# UCirKitUserStudy5.net
KiCad netlist of a schematic drawn in EAGLE
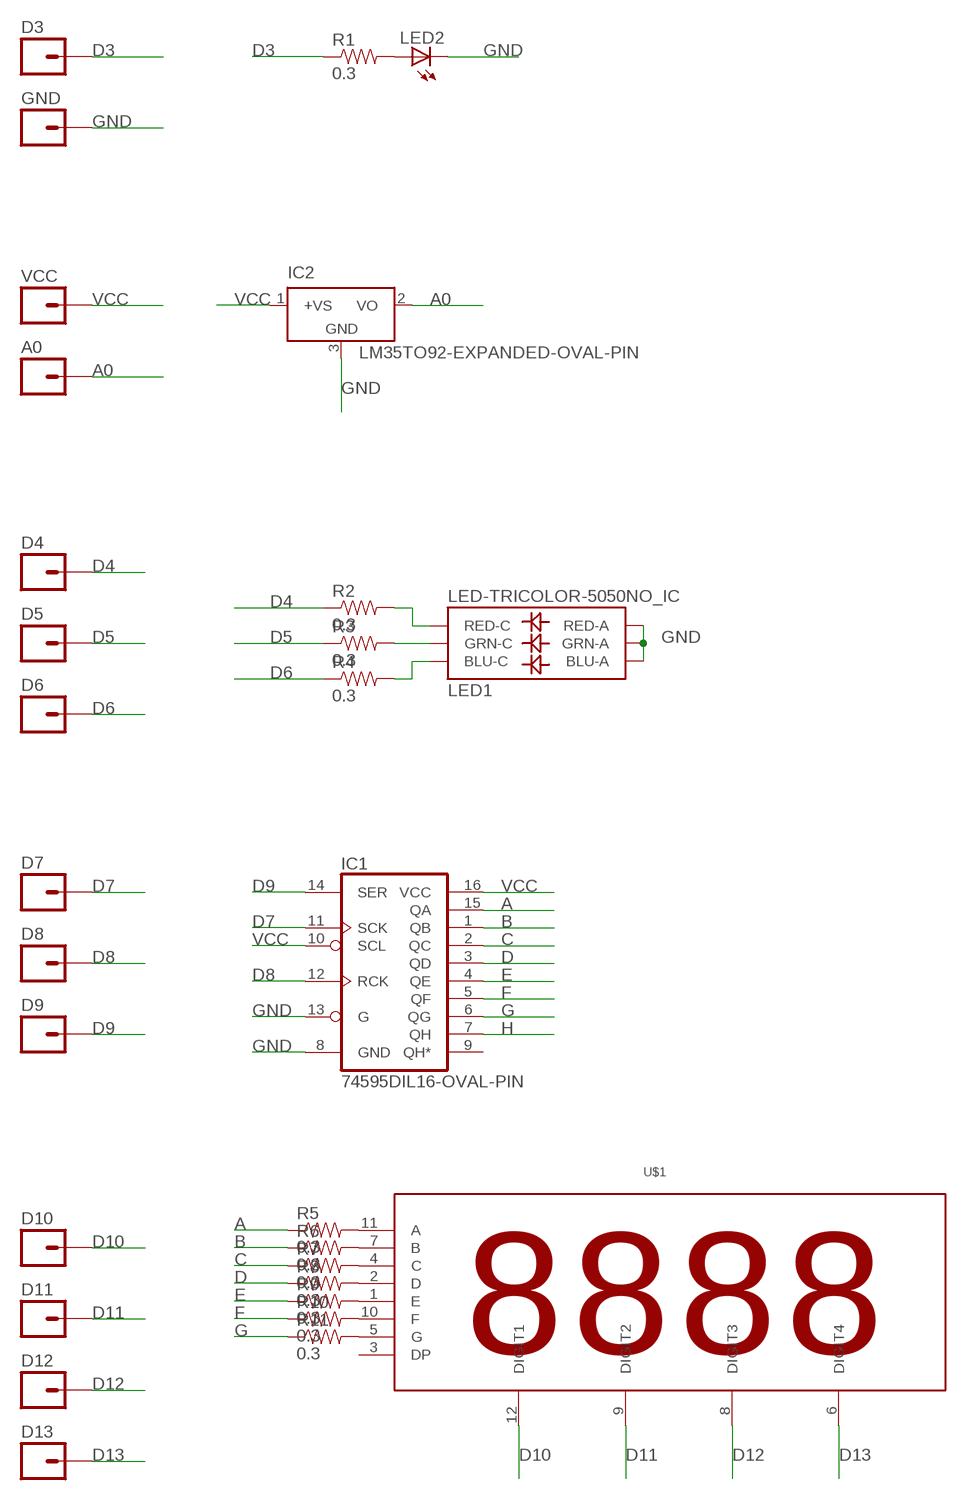
[diagram p0: schematic, sheet 1]

(export (version "E")
  (design (tool "Eeschema 10.0.6"))
  (components
    (comp (ref "A0")
      (value "M01OVAL_PIN")
      (footprint "eagle-import:1X01_OVAL_PIN")
      (libsource (lib "eagle-import") (part "M01OVAL_PIN"))
    )
    (comp (ref "D3")
      (value "M01OVAL_PIN")
      (footprint "eagle-import:1X01_OVAL_PIN")
      (libsource (lib "eagle-import") (part "M01OVAL_PIN"))
    )
    (comp (ref "D4")
      (value "M01OVAL_PIN")
      (footprint "eagle-import:1X01_OVAL_PIN")
      (libsource (lib "eagle-import") (part "M01OVAL_PIN"))
    )
    (comp (ref "D5")
      (value "M01OVAL_PIN")
      (footprint "eagle-import:1X01_OVAL_PIN")
      (libsource (lib "eagle-import") (part "M01OVAL_PIN"))
    )
    (comp (ref "D6")
      (value "M01OVAL_PIN")
      (footprint "eagle-import:1X01_OVAL_PIN")
      (libsource (lib "eagle-import") (part "M01OVAL_PIN"))
    )
    (comp (ref "D7")
      (value "M01OVAL_PIN")
      (footprint "eagle-import:1X01_OVAL_PIN")
      (libsource (lib "eagle-import") (part "M01OVAL_PIN"))
    )
    (comp (ref "D8")
      (value "M01OVAL_PIN")
      (footprint "eagle-import:1X01_OVAL_PIN")
      (libsource (lib "eagle-import") (part "M01OVAL_PIN"))
    )
    (comp (ref "D9")
      (value "M01OVAL_PIN")
      (footprint "eagle-import:1X01_OVAL_PIN")
      (libsource (lib "eagle-import") (part "M01OVAL_PIN"))
    )
    (comp (ref "D10")
      (value "M01OVAL_PIN")
      (footprint "eagle-import:1X01_OVAL_PIN")
      (libsource (lib "eagle-import") (part "M01OVAL_PIN"))
    )
    (comp (ref "D11")
      (value "M01OVAL_PIN")
      (footprint "eagle-import:1X01_OVAL_PIN")
      (libsource (lib "eagle-import") (part "M01OVAL_PIN"))
    )
    (comp (ref "D12")
      (value "M01OVAL_PIN")
      (footprint "eagle-import:1X01_OVAL_PIN")
      (libsource (lib "eagle-import") (part "M01OVAL_PIN"))
    )
    (comp (ref "D13")
      (value "M01OVAL_PIN")
      (footprint "eagle-import:1X01_OVAL_PIN")
      (libsource (lib "eagle-import") (part "M01OVAL_PIN"))
    )
    (comp (ref "GND")
      (value "M01OVAL_PIN")
      (footprint "eagle-import:1X01_OVAL_PIN")
      (libsource (lib "eagle-import") (part "M01OVAL_PIN"))
    )
    (comp (ref "IC1")
      (value "74595DIL16-OVAL-PIN")
      (footprint "eagle-import:DIL16-OVAL-PIN")
      (libsource (lib "eagle-import") (part "74595DIL16-OVAL-PIN"))
    )
    (comp (ref "IC2")
      (value "LM35TO92-EXPANDED-OVAL-PIN")
      (footprint "eagle-import:TO92-EXPANDED-OVAL-PIN")
      (libsource (lib "eagle-import") (part "LM35TO92-EXPANDED-OVAL-PIN"))
    )
    (comp (ref "LED1")
      (value "LED-TRICOLOR-5050NO_IC")
      (footprint "eagle-import:LED-TRICOLOR-5050")
      (libsource (lib "eagle-import") (part "LED-TRICOLOR-5050NO_IC"))
    )
    (comp (ref "LED2")
      (value "LEDCHIP-LED0805")
      (footprint "eagle-import:CHIP-LED0805")
      (libsource (lib "eagle-import") (part "LEDCHIP-LED0805"))
    )
    (comp (ref "R1")
      (value "0.3")
      (footprint "eagle-import:0805")
      (libsource (lib "eagle-import") (part "0.3OHM-1/8W-1%(0805)"))
    )
    (comp (ref "R2")
      (value "0.3")
      (footprint "eagle-import:0805")
      (libsource (lib "eagle-import") (part "0.3OHM-1/8W-1%(0805)"))
    )
    (comp (ref "R3")
      (value "0.3")
      (footprint "eagle-import:0805")
      (libsource (lib "eagle-import") (part "0.3OHM-1/8W-1%(0805)"))
    )
    (comp (ref "R4")
      (value "0.3")
      (footprint "eagle-import:0805")
      (libsource (lib "eagle-import") (part "0.3OHM-1/8W-1%(0805)"))
    )
    (comp (ref "R5")
      (value "0.3")
      (footprint "eagle-import:0805")
      (libsource (lib "eagle-import") (part "0.3OHM-1/8W-1%(0805)"))
    )
    (comp (ref "R6")
      (value "0.3")
      (footprint "eagle-import:0805")
      (libsource (lib "eagle-import") (part "0.3OHM-1/8W-1%(0805)"))
    )
    (comp (ref "R7")
      (value "0.3")
      (footprint "eagle-import:0805")
      (libsource (lib "eagle-import") (part "0.3OHM-1/8W-1%(0805)"))
    )
    (comp (ref "R8")
      (value "0.3")
      (footprint "eagle-import:0805")
      (libsource (lib "eagle-import") (part "0.3OHM-1/8W-1%(0805)"))
    )
    (comp (ref "R9")
      (value "0.3")
      (footprint "eagle-import:0805")
      (libsource (lib "eagle-import") (part "0.3OHM-1/8W-1%(0805)"))
    )
    (comp (ref "R10")
      (value "0.3")
      (footprint "eagle-import:0805")
      (libsource (lib "eagle-import") (part "0.3OHM-1/8W-1%(0805)"))
    )
    (comp (ref "R11")
      (value "0.3")
      (footprint "eagle-import:0805")
      (libsource (lib "eagle-import") (part "0.3OHM-1/8W-1%(0805)"))
    )
    (comp (ref "U$1")
      (value "4DIGIT_SEVEN_SEGMENT4DIGIT_SEVEN_SEGMENT_OVAL_PIN")
      (footprint "eagle-import:4DIGIT_SEVEN_SEGMENT_OVAL_PIN")
      (libsource (lib "eagle-import") (part "4DIGIT_SEVEN_SEGMENT4DIGIT_SEVEN_SEGMENT_OVAL_PIN"))
    )
    (comp (ref "VCC")
      (value "M01OVAL_PIN")
      (footprint "eagle-import:1X01_OVAL_PIN")
      (libsource (lib "eagle-import") (part "M01OVAL_PIN"))
    )
  )
  (nets
    (net (code "1") (name "/A") (class "Default")
      (node (ref "IC1") (pin "15") (pinfunction "QA_15") (pintype "tri_state"))
      (node (ref "R5") (pin "1") (pinfunction "1_1") (pintype "passive"))
    )
    (net (code "2") (name "/A0") (class "Default")
      (node (ref "A0") (pin "1") (pinfunction "1_1") (pintype "passive"))
      (node (ref "IC2") (pin "2") (pinfunction "VO_2") (pintype "input"))
    )
    (net (code "3") (name "/B") (class "Default")
      (node (ref "IC1") (pin "1") (pinfunction "QB_1") (pintype "tri_state"))
      (node (ref "R6") (pin "1") (pinfunction "1_1") (pintype "passive"))
    )
    (net (code "4") (name "/C") (class "Default")
      (node (ref "IC1") (pin "2") (pinfunction "QC_2") (pintype "tri_state"))
      (node (ref "R7") (pin "1") (pinfunction "1_1") (pintype "passive"))
    )
    (net (code "5") (name "/D") (class "Default")
      (node (ref "IC1") (pin "3") (pinfunction "QD_3") (pintype "tri_state"))
      (node (ref "R8") (pin "1") (pinfunction "1_1") (pintype "passive"))
    )
    (net (code "6") (name "/D3") (class "Default")
      (node (ref "D3") (pin "1") (pinfunction "1_1") (pintype "passive"))
      (node (ref "R1") (pin "1") (pinfunction "1_1") (pintype "passive"))
    )
    (net (code "7") (name "/D4") (class "Default")
      (node (ref "D4") (pin "1") (pinfunction "1_1") (pintype "passive"))
      (node (ref "R2") (pin "1") (pinfunction "1_1") (pintype "passive"))
    )
    (net (code "8") (name "/D5") (class "Default")
      (node (ref "D5") (pin "1") (pinfunction "1_1") (pintype "passive"))
      (node (ref "R3") (pin "1") (pinfunction "1_1") (pintype "passive"))
    )
    (net (code "9") (name "/D6") (class "Default")
      (node (ref "D6") (pin "1") (pinfunction "1_1") (pintype "passive"))
      (node (ref "R4") (pin "1") (pinfunction "1_1") (pintype "passive"))
    )
    (net (code "10") (name "/D7") (class "Default")
      (node (ref "D7") (pin "1") (pinfunction "1_1") (pintype "passive"))
      (node (ref "IC1") (pin "11") (pinfunction "SCK_11") (pintype "input"))
    )
    (net (code "11") (name "/D8") (class "Default")
      (node (ref "D8") (pin "1") (pinfunction "1_1") (pintype "passive"))
      (node (ref "IC1") (pin "12") (pinfunction "RCK_12") (pintype "input"))
    )
    (net (code "12") (name "/D9") (class "Default")
      (node (ref "D9") (pin "1") (pinfunction "1_1") (pintype "passive"))
      (node (ref "IC1") (pin "14") (pinfunction "SER_14") (pintype "input"))
    )
    (net (code "13") (name "/D10") (class "Default")
      (node (ref "D10") (pin "1") (pinfunction "1_1") (pintype "passive"))
      (node (ref "U$1") (pin "12") (pinfunction "DIGIT1_12") (pintype "bidirectional"))
    )
    (net (code "14") (name "/D11") (class "Default")
      (node (ref "D11") (pin "1") (pinfunction "1_1") (pintype "passive"))
      (node (ref "U$1") (pin "9") (pinfunction "DIGIT2_9") (pintype "bidirectional"))
    )
    (net (code "15") (name "/D12") (class "Default")
      (node (ref "D12") (pin "1") (pinfunction "1_1") (pintype "passive"))
      (node (ref "U$1") (pin "8") (pinfunction "DIGIT3_8") (pintype "bidirectional"))
    )
    (net (code "16") (name "/D13") (class "Default")
      (node (ref "D13") (pin "1") (pinfunction "1_1") (pintype "passive"))
      (node (ref "U$1") (pin "6") (pinfunction "DIGIT4_6") (pintype "bidirectional"))
    )
    (net (code "17") (name "/E") (class "Default")
      (node (ref "IC1") (pin "4") (pinfunction "QE_4") (pintype "tri_state"))
      (node (ref "R9") (pin "1") (pinfunction "1_1") (pintype "passive"))
    )
    (net (code "18") (name "/F") (class "Default")
      (node (ref "IC1") (pin "5") (pinfunction "QF_5") (pintype "tri_state"))
      (node (ref "R10") (pin "1") (pinfunction "1_1") (pintype "passive"))
    )
    (net (code "19") (name "/G") (class "Default")
      (node (ref "IC1") (pin "6") (pinfunction "QG_6") (pintype "tri_state"))
      (node (ref "R11") (pin "1") (pinfunction "1_1") (pintype "passive"))
    )
    (net (code "20") (name "/GND") (class "Default")
      (node (ref "GND") (pin "1") (pinfunction "1_1") (pintype "passive"))
      (node (ref "IC1") (pin "13") (pinfunction "G_13") (pintype "input"))
      (node (ref "IC1") (pin "8") (pinfunction "GND_8") (pintype "power_in"))
      (node (ref "IC2") (pin "3") (pinfunction "GND_3") (pintype "power_in"))
      (node (ref "LED1") (pin "1") (pinfunction "GRN-A_1") (pintype "bidirectional"))
      (node (ref "LED1") (pin "2") (pinfunction "RED-A_2") (pintype "bidirectional"))
      (node (ref "LED1") (pin "3") (pinfunction "BLU-A_3") (pintype "bidirectional"))
      (node (ref "LED2") (pin "C") (pinfunction "C_C") (pintype "passive"))
    )
    (net (code "21") (name "/H") (class "Default")
      (node (ref "IC1") (pin "7") (pinfunction "QH_7") (pintype "tri_state"))
    )
    (net (code "22") (name "/VCC") (class "Default")
      (node (ref "IC1") (pin "10") (pinfunction "SCL_10") (pintype "input"))
      (node (ref "IC1") (pin "16") (pinfunction "VCC_16") (pintype "power_in"))
      (node (ref "IC2") (pin "1") (pinfunction "+VS_1") (pintype "input"))
      (node (ref "VCC") (pin "1") (pinfunction "1_1") (pintype "passive"))
    )
    (net (code "23") (name "Net-(LED1-BLU-C)") (class "Default")
      (node (ref "LED1") (pin "4") (pinfunction "BLU-C_4") (pintype "bidirectional"))
      (node (ref "R4") (pin "2") (pinfunction "2_2") (pintype "passive"))
    )
    (net (code "24") (name "Net-(LED1-GRN-C)") (class "Default")
      (node (ref "LED1") (pin "6") (pinfunction "GRN-C_6") (pintype "bidirectional"))
      (node (ref "R3") (pin "2") (pinfunction "2_2") (pintype "passive"))
    )
    (net (code "25") (name "Net-(LED1-RED-C)") (class "Default")
      (node (ref "LED1") (pin "5") (pinfunction "RED-C_5") (pintype "bidirectional"))
      (node (ref "R2") (pin "2") (pinfunction "2_2") (pintype "passive"))
    )
    (net (code "26") (name "Net-(LED2-PadA)") (class "Default")
      (node (ref "LED2") (pin "A") (pinfunction "A_A") (pintype "passive"))
      (node (ref "R1") (pin "2") (pinfunction "2_2") (pintype "passive"))
    )
    (net (code "27") (name "Net-(U$1-A)") (class "Default")
      (node (ref "R5") (pin "2") (pinfunction "2_2") (pintype "passive"))
      (node (ref "U$1") (pin "11") (pinfunction "A_11") (pintype "bidirectional"))
    )
    (net (code "28") (name "Net-(U$1-B)") (class "Default")
      (node (ref "R6") (pin "2") (pinfunction "2_2") (pintype "passive"))
      (node (ref "U$1") (pin "7") (pinfunction "B_7") (pintype "bidirectional"))
    )
    (net (code "29") (name "Net-(U$1-C)") (class "Default")
      (node (ref "R7") (pin "2") (pinfunction "2_2") (pintype "passive"))
      (node (ref "U$1") (pin "4") (pinfunction "C_4") (pintype "bidirectional"))
    )
    (net (code "30") (name "Net-(U$1-D)") (class "Default")
      (node (ref "R8") (pin "2") (pinfunction "2_2") (pintype "passive"))
      (node (ref "U$1") (pin "2") (pinfunction "D_2") (pintype "bidirectional"))
    )
    (net (code "31") (name "Net-(U$1-E)") (class "Default")
      (node (ref "R9") (pin "2") (pinfunction "2_2") (pintype "passive"))
      (node (ref "U$1") (pin "1") (pinfunction "E_1") (pintype "bidirectional"))
    )
    (net (code "32") (name "Net-(U$1-F)") (class "Default")
      (node (ref "R10") (pin "2") (pinfunction "2_2") (pintype "passive"))
      (node (ref "U$1") (pin "10") (pinfunction "F_10") (pintype "bidirectional"))
    )
    (net (code "33") (name "Net-(U$1-G)") (class "Default")
      (node (ref "R11") (pin "2") (pinfunction "2_2") (pintype "passive"))
      (node (ref "U$1") (pin "5") (pinfunction "G_5") (pintype "bidirectional"))
    )
    (net (code "34") (name "unconnected-(IC1-QH*-Pad9)") (class "Default")
      (node (ref "IC1") (pin "9") (pinfunction "QH*_9") (pintype "tri_state"))
    )
    (net (code "35") (name "unconnected-(U$1-DP-Pad3)") (class "Default")
      (node (ref "U$1") (pin "3") (pinfunction "DP_3") (pintype "bidirectional"))
    )
  )
)
